# pic24rgb01-r3.net
KiCad netlist of a schematic drawn in EAGLE
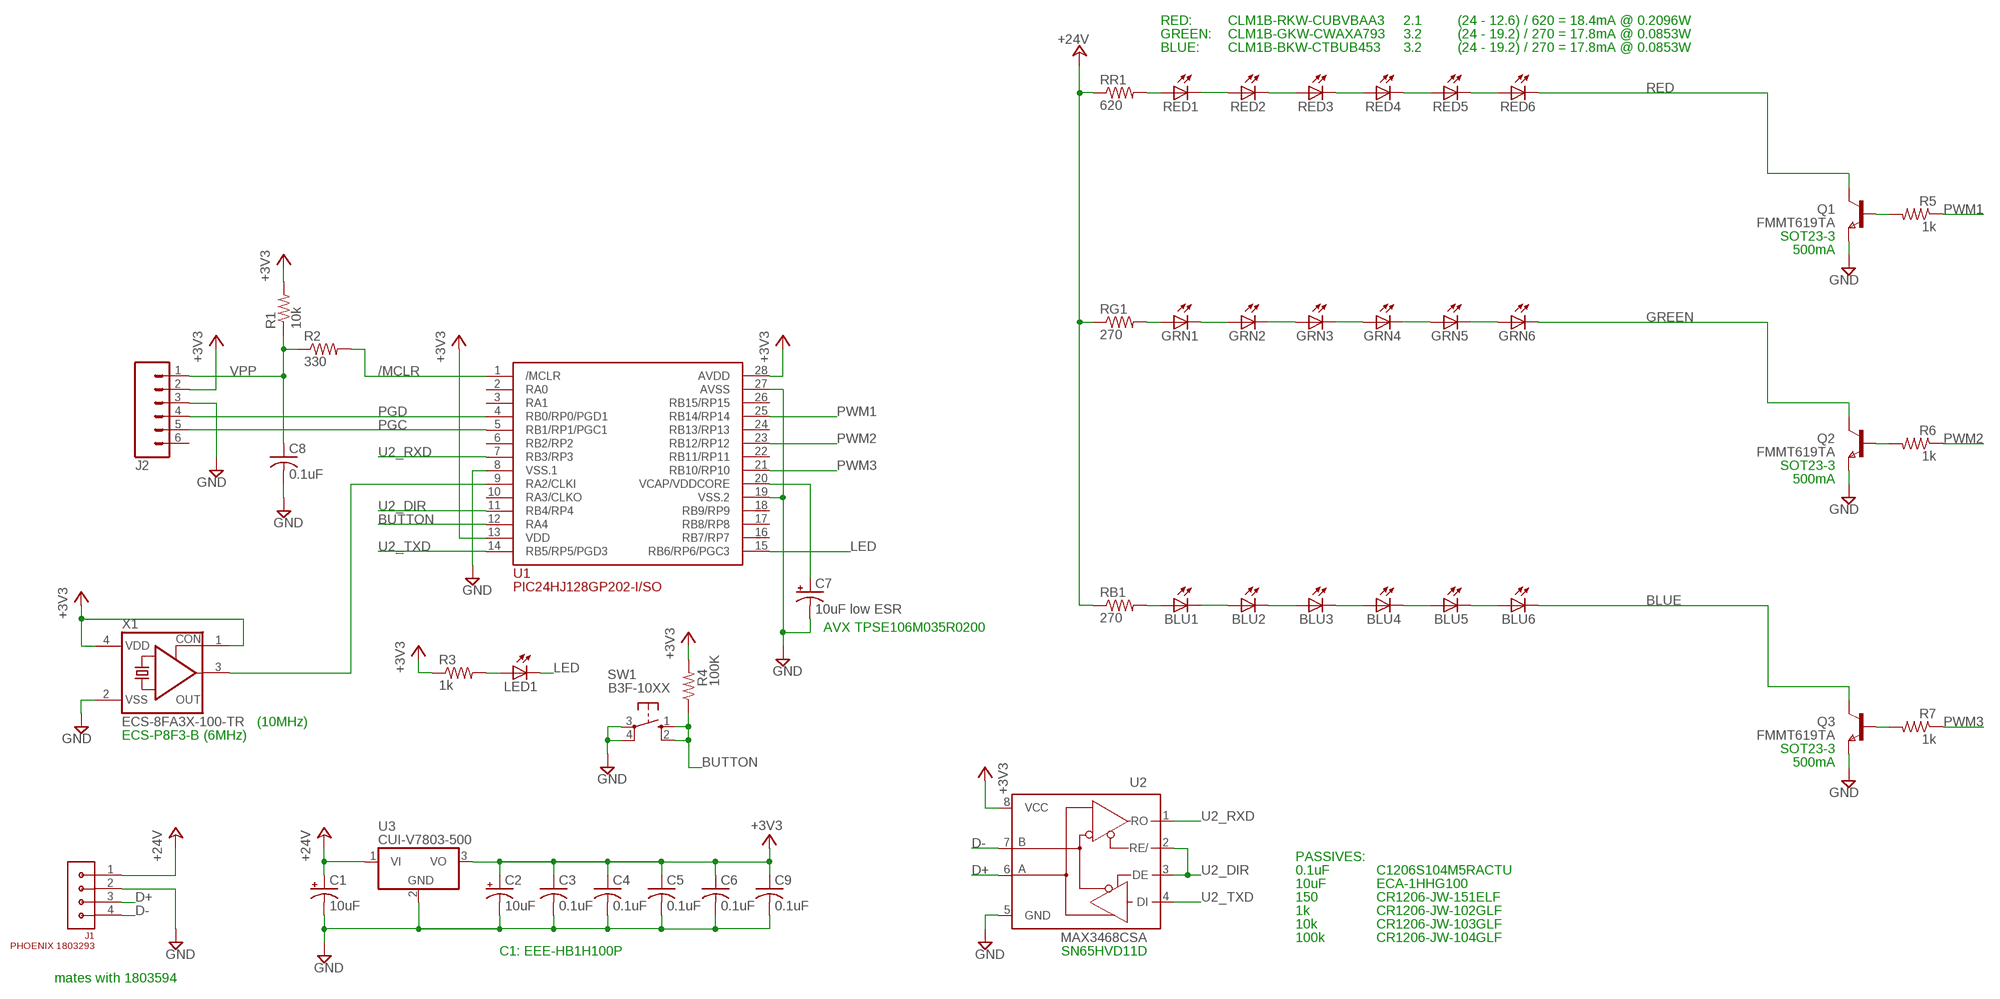
[diagram p0: schematic, sheet 1]

(export (version "E")
  (design (tool "Eeschema 10.0.6"))
  (components
    (comp (ref "BLU1")
      (value "LEDKA-3528ASYC")
      (footprint "eagle-import:KA-3528ASYC")
      (libsource (lib "eagle-import") (part "LEDKA-3528ASYC"))
    )
    (comp (ref "BLU2")
      (value "LEDKA-3528ASYC")
      (footprint "eagle-import:KA-3528ASYC")
      (libsource (lib "eagle-import") (part "LEDKA-3528ASYC"))
    )
    (comp (ref "BLU3")
      (value "LEDKA-3528ASYC")
      (footprint "eagle-import:KA-3528ASYC")
      (libsource (lib "eagle-import") (part "LEDKA-3528ASYC"))
    )
    (comp (ref "BLU4")
      (value "LEDKA-3528ASYC")
      (footprint "eagle-import:KA-3528ASYC")
      (libsource (lib "eagle-import") (part "LEDKA-3528ASYC"))
    )
    (comp (ref "BLU5")
      (value "LEDKA-3528ASYC")
      (footprint "eagle-import:KA-3528ASYC")
      (libsource (lib "eagle-import") (part "LEDKA-3528ASYC"))
    )
    (comp (ref "BLU6")
      (value "LEDKA-3528ASYC")
      (footprint "eagle-import:KA-3528ASYC")
      (libsource (lib "eagle-import") (part "LEDKA-3528ASYC"))
    )
    (comp (ref "C1")
      (value "10uF")
      (footprint "eagle-import:PANASONIC_D")
      (libsource (lib "eagle-import") (part "CPOL-USD"))
    )
    (comp (ref "C2")
      (value "10uF")
      (footprint "eagle-import:PANASONIC_D")
      (libsource (lib "eagle-import") (part "CPOL-USD"))
    )
    (comp (ref "C3")
      (value "0.1uF")
      (footprint "eagle-import:C1206")
      (libsource (lib "eagle-import") (part "C-USC1206"))
    )
    (comp (ref "C4")
      (value "0.1uF")
      (footprint "eagle-import:C1206")
      (libsource (lib "eagle-import") (part "C-USC1206"))
    )
    (comp (ref "C5")
      (value "0.1uF")
      (footprint "eagle-import:C1206")
      (libsource (lib "eagle-import") (part "C-USC1206"))
    )
    (comp (ref "C6")
      (value "0.1uF")
      (footprint "eagle-import:C1206")
      (libsource (lib "eagle-import") (part "C-USC1206"))
    )
    (comp (ref "C7")
      (value "10uF low ESR")
      (footprint "eagle-import:D_7343-31R")
      (libsource (lib "eagle-import") (part "CPOL-USD/7343-31R"))
    )
    (comp (ref "C8")
      (value "0.1uF")
      (footprint "eagle-import:C1206")
      (libsource (lib "eagle-import") (part "C-USC1206"))
    )
    (comp (ref "C9")
      (value "0.1uF")
      (footprint "eagle-import:C1206")
      (libsource (lib "eagle-import") (part "C-USC1206"))
    )
    (comp (ref "GRN1")
      (value "LEDKA-3528ASYC")
      (footprint "eagle-import:KA-3528ASYC")
      (libsource (lib "eagle-import") (part "LEDKA-3528ASYC"))
    )
    (comp (ref "GRN2")
      (value "LEDKA-3528ASYC")
      (footprint "eagle-import:KA-3528ASYC")
      (libsource (lib "eagle-import") (part "LEDKA-3528ASYC"))
    )
    (comp (ref "GRN3")
      (value "LEDKA-3528ASYC")
      (footprint "eagle-import:KA-3528ASYC")
      (libsource (lib "eagle-import") (part "LEDKA-3528ASYC"))
    )
    (comp (ref "GRN4")
      (value "LEDKA-3528ASYC")
      (footprint "eagle-import:KA-3528ASYC")
      (libsource (lib "eagle-import") (part "LEDKA-3528ASYC"))
    )
    (comp (ref "GRN5")
      (value "LEDKA-3528ASYC")
      (footprint "eagle-import:KA-3528ASYC")
      (libsource (lib "eagle-import") (part "LEDKA-3528ASYC"))
    )
    (comp (ref "GRN6")
      (value "LEDKA-3528ASYC")
      (footprint "eagle-import:KA-3528ASYC")
      (libsource (lib "eagle-import") (part "LEDKA-3528ASYC"))
    )
    (comp (ref "J1")
      (value "PHOENIX 1803293")
      (footprint "eagle-import:CON-PHOENIX-1803293-3.81-1X4")
      (libsource (lib "eagle-import") (part "CON-3.81MM-1X4-PHOENIX-1803293"))
    )
    (comp (ref "J2")
      (value "M06SIP")
      (footprint "eagle-import:1X06")
      (libsource (lib "eagle-import") (part "M06SIP"))
    )
    (comp (ref "LED1")
      (value "LED3MM")
      (footprint "eagle-import:LED3MM")
      (libsource (lib "eagle-import") (part "LED3MM"))
    )
    (comp (ref "Q1")
      (value "FMMT619TA")
      (footprint "eagle-import:SOT-23")
      (fields (field (name "MPN") "DSS20201L-7"))
      (libsource (lib "eagle-import") (part "NPNSOT23"))
    )
    (comp (ref "Q2")
      (value "FMMT619TA")
      (footprint "eagle-import:SOT-23")
      (fields (field (name "MPN") "DSS20201L-7"))
      (libsource (lib "eagle-import") (part "NPNSOT23"))
    )
    (comp (ref "Q3")
      (value "FMMT619TA")
      (footprint "eagle-import:SOT-23")
      (fields (field (name "MPN") "DSS20201L-7"))
      (libsource (lib "eagle-import") (part "NPNSOT23"))
    )
    (comp (ref "R1")
      (value "10k")
      (footprint "eagle-import:R1206")
      (libsource (lib "eagle-import") (part "R-US_R1206"))
    )
    (comp (ref "R2")
      (value "330")
      (footprint "eagle-import:R1206")
      (libsource (lib "eagle-import") (part "R-US_R1206"))
    )
    (comp (ref "R3")
      (value "1k")
      (footprint "eagle-import:R1206")
      (libsource (lib "eagle-import") (part "R-US_R1206"))
    )
    (comp (ref "R4")
      (value "100K")
      (footprint "eagle-import:M1206")
      (libsource (lib "eagle-import") (part "R-US_M1206"))
    )
    (comp (ref "R5")
      (value "1k")
      (footprint "eagle-import:R1206")
      (libsource (lib "eagle-import") (part "R-US_R1206"))
    )
    (comp (ref "R6")
      (value "1k")
      (footprint "eagle-import:R1206")
      (libsource (lib "eagle-import") (part "R-US_R1206"))
    )
    (comp (ref "R7")
      (value "1k")
      (footprint "eagle-import:R1206")
      (libsource (lib "eagle-import") (part "R-US_R1206"))
    )
    (comp (ref "RB1")
      (value "270")
      (footprint "eagle-import:R1206")
      (libsource (lib "eagle-import") (part "R-US_R1206"))
    )
    (comp (ref "RED1")
      (value "LEDKA-3528ASYC")
      (footprint "eagle-import:KA-3528ASYC")
      (libsource (lib "eagle-import") (part "LEDKA-3528ASYC"))
    )
    (comp (ref "RED2")
      (value "LEDKA-3528ASYC")
      (footprint "eagle-import:KA-3528ASYC")
      (libsource (lib "eagle-import") (part "LEDKA-3528ASYC"))
    )
    (comp (ref "RED3")
      (value "LEDKA-3528ASYC")
      (footprint "eagle-import:KA-3528ASYC")
      (libsource (lib "eagle-import") (part "LEDKA-3528ASYC"))
    )
    (comp (ref "RED4")
      (value "LEDKA-3528ASYC")
      (footprint "eagle-import:KA-3528ASYC")
      (libsource (lib "eagle-import") (part "LEDKA-3528ASYC"))
    )
    (comp (ref "RED5")
      (value "LEDKA-3528ASYC")
      (footprint "eagle-import:KA-3528ASYC")
      (libsource (lib "eagle-import") (part "LEDKA-3528ASYC"))
    )
    (comp (ref "RED6")
      (value "LEDKA-3528ASYC")
      (footprint "eagle-import:KA-3528ASYC")
      (libsource (lib "eagle-import") (part "LEDKA-3528ASYC"))
    )
    (comp (ref "RG1")
      (value "270")
      (footprint "eagle-import:R1206")
      (libsource (lib "eagle-import") (part "R-US_R1206"))
    )
    (comp (ref "RR1")
      (value "620")
      (footprint "eagle-import:R1206")
      (libsource (lib "eagle-import") (part "R-US_R1206"))
    )
    (comp (ref "SW1")
      (value "B3F-10XX")
      (footprint "eagle-import:B3F-10XX")
      (libsource (lib "eagle-import") (part "10-XX"))
    )
    (comp (ref "U1")
      (value "PIC24HJ128GP202-I/SO")
      (footprint "eagle-import:SO28W")
      (libsource (lib "eagle-import") (part "PIC24HJ128GP202-I/SO"))
    )
    (comp (ref "U2")
      (value "MAX3468CSA")
      (footprint "eagle-import:SO08")
      (fields (field (name "MPN") "MAX3468CSA+"))
      (libsource (lib "eagle-import") (part "MAX34SA68C"))
    )
    (comp (ref "U3")
      (value "CUI-V7803-500")
      (footprint "eagle-import:CUI-78XX-500")
      (libsource (lib "eagle-import") (part "CUI-V7803-500"))
    )
    (comp (ref "X1")
      (value "ECS-8FA3X-100-TR")
      (footprint "eagle-import:1100S")
      (libsource (lib "eagle-import") (part "CRYSTAL_RES-1100S"))
    )
  )
  (nets
    (net (code "1") (name "+3V3") (class "Default")
      (node (ref "C2") (pin "+") (pinfunction "+_+") (pintype "passive"))
      (node (ref "C3") (pin "1") (pinfunction "1_1") (pintype "passive"))
      (node (ref "C4") (pin "1") (pinfunction "1_1") (pintype "passive"))
      (node (ref "C5") (pin "1") (pinfunction "1_1") (pintype "passive"))
      (node (ref "C6") (pin "1") (pinfunction "1_1") (pintype "passive"))
      (node (ref "C9") (pin "1") (pinfunction "1_1") (pintype "passive"))
      (node (ref "J2") (pin "2") (pinfunction "2_2") (pintype "passive"))
      (node (ref "R1") (pin "2") (pinfunction "2_2") (pintype "passive"))
      (node (ref "R3") (pin "1") (pinfunction "1_1") (pintype "passive"))
      (node (ref "R4") (pin "2") (pinfunction "2_2") (pintype "passive"))
      (node (ref "U1") (pin "13") (pinfunction "VDD_13") (pintype "bidirectional"))
      (node (ref "U1") (pin "28") (pinfunction "AVDD_28") (pintype "bidirectional"))
      (node (ref "U2") (pin "8") (pinfunction "VCC_8") (pintype "power_in"))
      (node (ref "U3") (pin "3") (pinfunction "VO_3") (pintype "passive"))
      (node (ref "X1") (pin "1") (pinfunction "CON_1") (pintype "input"))
      (node (ref "X1") (pin "4") (pinfunction "VDD_4") (pintype "power_in"))
    )
    (net (code "2") (name "+24V") (class "Default")
      (node (ref "C1") (pin "+") (pinfunction "+_+") (pintype "passive"))
      (node (ref "J1") (pin "1") (pinfunction "1_1") (pintype "bidirectional"))
      (node (ref "RB1") (pin "1") (pinfunction "1_1") (pintype "passive"))
      (node (ref "RG1") (pin "1") (pinfunction "1_1") (pintype "passive"))
      (node (ref "RR1") (pin "1") (pinfunction "1_1") (pintype "passive"))
      (node (ref "U3") (pin "1") (pinfunction "VI_1") (pintype "input"))
    )
    (net (code "3") (name "/BLUE") (class "Default")
      (node (ref "BLU6") (pin "C") (pinfunction "C_C") (pintype "passive"))
      (node (ref "Q3") (pin "1") (pinfunction "C_1") (pintype "passive"))
    )
    (net (code "4") (name "/BUTTON") (class "Default")
      (node (ref "R4") (pin "1") (pinfunction "1_1") (pintype "passive"))
      (node (ref "SW1") (pin "1") (pinfunction "S_1") (pintype "passive"))
      (node (ref "SW1") (pin "2") (pinfunction "S1_2") (pintype "passive"))
      (node (ref "U1") (pin "12") (pinfunction "RA4_12") (pintype "bidirectional"))
    )
    (net (code "5") (name "/D+") (class "Default")
      (node (ref "J1") (pin "3") (pinfunction "3_3") (pintype "bidirectional"))
      (node (ref "U2") (pin "6") (pinfunction "A_6") (pintype "passive"))
    )
    (net (code "6") (name "/D-") (class "Default")
      (node (ref "J1") (pin "4") (pinfunction "4_4") (pintype "bidirectional"))
      (node (ref "U2") (pin "7") (pinfunction "B_7") (pintype "passive"))
    )
    (net (code "7") (name "/GREEN") (class "Default")
      (node (ref "GRN6") (pin "C") (pinfunction "C_C") (pintype "passive"))
      (node (ref "Q2") (pin "1") (pinfunction "C_1") (pintype "passive"))
    )
    (net (code "8") (name "/LED") (class "Default")
      (node (ref "LED1") (pin "K") (pinfunction "C_K") (pintype "passive"))
      (node (ref "U1") (pin "15") (pinfunction "RB6/RP6/PGC3_15") (pintype "bidirectional"))
    )
    (net (code "9") (name "/PGC") (class "Default")
      (node (ref "J2") (pin "5") (pinfunction "5_5") (pintype "passive"))
      (node (ref "U1") (pin "5") (pinfunction "RB1/RP1/PGC1_5") (pintype "bidirectional"))
    )
    (net (code "10") (name "/PGD") (class "Default")
      (node (ref "J2") (pin "4") (pinfunction "4_4") (pintype "passive"))
      (node (ref "U1") (pin "4") (pinfunction "RB0/RP0/PGD1_4") (pintype "bidirectional"))
    )
    (net (code "11") (name "/PWM1") (class "Default")
      (node (ref "R5") (pin "1") (pinfunction "1_1") (pintype "passive"))
      (node (ref "U1") (pin "25") (pinfunction "RB14/RP14_25") (pintype "bidirectional"))
    )
    (net (code "12") (name "/PWM2") (class "Default")
      (node (ref "R6") (pin "1") (pinfunction "1_1") (pintype "passive"))
      (node (ref "U1") (pin "23") (pinfunction "RB12/RP12_23") (pintype "bidirectional"))
    )
    (net (code "13") (name "/PWM3") (class "Default")
      (node (ref "R7") (pin "1") (pinfunction "1_1") (pintype "passive"))
      (node (ref "U1") (pin "21") (pinfunction "RB10/RP10_21") (pintype "bidirectional"))
    )
    (net (code "14") (name "/RED") (class "Default")
      (node (ref "Q1") (pin "1") (pinfunction "C_1") (pintype "passive"))
      (node (ref "RED6") (pin "C") (pinfunction "C_C") (pintype "passive"))
    )
    (net (code "15") (name "/U2_DIR") (class "Default")
      (node (ref "U1") (pin "11") (pinfunction "RB4/RP4_11") (pintype "bidirectional"))
      (node (ref "U2") (pin "2") (pinfunction "RE/_2") (pintype "input"))
      (node (ref "U2") (pin "3") (pinfunction "DE_3") (pintype "input"))
    )
    (net (code "16") (name "/U2_RXD") (class "Default")
      (node (ref "U1") (pin "7") (pinfunction "RB3/RP3_7") (pintype "bidirectional"))
      (node (ref "U2") (pin "1") (pinfunction "RO_1") (pintype "output"))
    )
    (net (code "17") (name "/U2_TXD") (class "Default")
      (node (ref "U1") (pin "14") (pinfunction "RB5/RP5/PGD3_14") (pintype "bidirectional"))
      (node (ref "U2") (pin "4") (pinfunction "DI_4") (pintype "input"))
    )
    (net (code "18") (name "/VPP") (class "Default")
      (node (ref "C8") (pin "1") (pinfunction "1_1") (pintype "passive"))
      (node (ref "J2") (pin "1") (pinfunction "1_1") (pintype "passive"))
      (node (ref "R1") (pin "1") (pinfunction "1_1") (pintype "passive"))
      (node (ref "R2") (pin "1") (pinfunction "1_1") (pintype "passive"))
    )
    (net (code "19") (name "/{slash}MCLR") (class "Default")
      (node (ref "R2") (pin "2") (pinfunction "2_2") (pintype "passive"))
      (node (ref "U1") (pin "1") (pinfunction "/MCLR_1") (pintype "bidirectional"))
    )
    (net (code "20") (name "GND") (class "Default")
      (node (ref "C1") (pin "-") (pinfunction "-_-") (pintype "passive"))
      (node (ref "C2") (pin "-") (pinfunction "-_-") (pintype "passive"))
      (node (ref "C3") (pin "2") (pinfunction "2_2") (pintype "passive"))
      (node (ref "C4") (pin "2") (pinfunction "2_2") (pintype "passive"))
      (node (ref "C5") (pin "2") (pinfunction "2_2") (pintype "passive"))
      (node (ref "C6") (pin "2") (pinfunction "2_2") (pintype "passive"))
      (node (ref "C7") (pin "-") (pinfunction "-_-") (pintype "passive"))
      (node (ref "C8") (pin "2") (pinfunction "2_2") (pintype "passive"))
      (node (ref "C9") (pin "2") (pinfunction "2_2") (pintype "passive"))
      (node (ref "J1") (pin "2") (pinfunction "2_2") (pintype "bidirectional"))
      (node (ref "J2") (pin "3") (pinfunction "3_3") (pintype "passive"))
      (node (ref "Q1") (pin "2") (pinfunction "E_2") (pintype "passive"))
      (node (ref "Q2") (pin "2") (pinfunction "E_2") (pintype "passive"))
      (node (ref "Q3") (pin "2") (pinfunction "E_2") (pintype "passive"))
      (node (ref "SW1") (pin "3") (pinfunction "P_3") (pintype "passive"))
      (node (ref "SW1") (pin "4") (pinfunction "P1_4") (pintype "passive"))
      (node (ref "U1") (pin "19") (pinfunction "VSS.2_19") (pintype "bidirectional"))
      (node (ref "U1") (pin "27") (pinfunction "AVSS_27") (pintype "bidirectional"))
      (node (ref "U1") (pin "8") (pinfunction "VSS.1_8") (pintype "bidirectional"))
      (node (ref "U2") (pin "5") (pinfunction "GND_5") (pintype "power_in"))
      (node (ref "U3") (pin "2") (pinfunction "GND_2") (pintype "passive"))
      (node (ref "X1") (pin "2") (pinfunction "VSS_2") (pintype "power_in"))
    )
    (net (code "21") (name "Net-(BLU1-PadA)") (class "Default")
      (node (ref "BLU1") (pin "A") (pinfunction "A_A") (pintype "passive"))
      (node (ref "RB1") (pin "2") (pinfunction "2_2") (pintype "passive"))
    )
    (net (code "22") (name "Net-(BLU1-PadC)") (class "Default")
      (node (ref "BLU1") (pin "C") (pinfunction "C_C") (pintype "passive"))
      (node (ref "BLU2") (pin "A") (pinfunction "A_A") (pintype "passive"))
    )
    (net (code "23") (name "Net-(BLU2-PadC)") (class "Default")
      (node (ref "BLU2") (pin "C") (pinfunction "C_C") (pintype "passive"))
      (node (ref "BLU3") (pin "A") (pinfunction "A_A") (pintype "passive"))
    )
    (net (code "24") (name "Net-(BLU3-PadC)") (class "Default")
      (node (ref "BLU3") (pin "C") (pinfunction "C_C") (pintype "passive"))
      (node (ref "BLU4") (pin "A") (pinfunction "A_A") (pintype "passive"))
    )
    (net (code "25") (name "Net-(BLU4-PadC)") (class "Default")
      (node (ref "BLU4") (pin "C") (pinfunction "C_C") (pintype "passive"))
      (node (ref "BLU5") (pin "A") (pinfunction "A_A") (pintype "passive"))
    )
    (net (code "26") (name "Net-(BLU5-PadC)") (class "Default")
      (node (ref "BLU5") (pin "C") (pinfunction "C_C") (pintype "passive"))
      (node (ref "BLU6") (pin "A") (pinfunction "A_A") (pintype "passive"))
    )
    (net (code "27") (name "Net-(GRN1-PadA)") (class "Default")
      (node (ref "GRN1") (pin "A") (pinfunction "A_A") (pintype "passive"))
      (node (ref "RG1") (pin "2") (pinfunction "2_2") (pintype "passive"))
    )
    (net (code "28") (name "Net-(GRN1-PadC)") (class "Default")
      (node (ref "GRN1") (pin "C") (pinfunction "C_C") (pintype "passive"))
      (node (ref "GRN2") (pin "A") (pinfunction "A_A") (pintype "passive"))
    )
    (net (code "29") (name "Net-(GRN2-PadC)") (class "Default")
      (node (ref "GRN2") (pin "C") (pinfunction "C_C") (pintype "passive"))
      (node (ref "GRN3") (pin "A") (pinfunction "A_A") (pintype "passive"))
    )
    (net (code "30") (name "Net-(GRN3-PadC)") (class "Default")
      (node (ref "GRN3") (pin "C") (pinfunction "C_C") (pintype "passive"))
      (node (ref "GRN4") (pin "A") (pinfunction "A_A") (pintype "passive"))
    )
    (net (code "31") (name "Net-(GRN4-PadC)") (class "Default")
      (node (ref "GRN4") (pin "C") (pinfunction "C_C") (pintype "passive"))
      (node (ref "GRN5") (pin "A") (pinfunction "A_A") (pintype "passive"))
    )
    (net (code "32") (name "Net-(GRN5-PadC)") (class "Default")
      (node (ref "GRN5") (pin "C") (pinfunction "C_C") (pintype "passive"))
      (node (ref "GRN6") (pin "A") (pinfunction "A_A") (pintype "passive"))
    )
    (net (code "33") (name "Net-(LED1-PadA)") (class "Default")
      (node (ref "LED1") (pin "A") (pinfunction "A_A") (pintype "passive"))
      (node (ref "R3") (pin "2") (pinfunction "2_2") (pintype "passive"))
    )
    (net (code "34") (name "Net-(Q1-B)") (class "Default")
      (node (ref "Q1") (pin "3") (pinfunction "B_3") (pintype "passive"))
      (node (ref "R5") (pin "2") (pinfunction "2_2") (pintype "passive"))
    )
    (net (code "35") (name "Net-(Q2-B)") (class "Default")
      (node (ref "Q2") (pin "3") (pinfunction "B_3") (pintype "passive"))
      (node (ref "R6") (pin "2") (pinfunction "2_2") (pintype "passive"))
    )
    (net (code "36") (name "Net-(Q3-B)") (class "Default")
      (node (ref "Q3") (pin "3") (pinfunction "B_3") (pintype "passive"))
      (node (ref "R7") (pin "2") (pinfunction "2_2") (pintype "passive"))
    )
    (net (code "37") (name "Net-(RED1-PadA)") (class "Default")
      (node (ref "RED1") (pin "A") (pinfunction "A_A") (pintype "passive"))
      (node (ref "RR1") (pin "2") (pinfunction "2_2") (pintype "passive"))
    )
    (net (code "38") (name "Net-(RED1-PadC)") (class "Default")
      (node (ref "RED1") (pin "C") (pinfunction "C_C") (pintype "passive"))
      (node (ref "RED2") (pin "A") (pinfunction "A_A") (pintype "passive"))
    )
    (net (code "39") (name "Net-(RED2-PadC)") (class "Default")
      (node (ref "RED2") (pin "C") (pinfunction "C_C") (pintype "passive"))
      (node (ref "RED3") (pin "A") (pinfunction "A_A") (pintype "passive"))
    )
    (net (code "40") (name "Net-(RED3-PadC)") (class "Default")
      (node (ref "RED3") (pin "C") (pinfunction "C_C") (pintype "passive"))
      (node (ref "RED4") (pin "A") (pinfunction "A_A") (pintype "passive"))
    )
    (net (code "41") (name "Net-(RED4-PadC)") (class "Default")
      (node (ref "RED4") (pin "C") (pinfunction "C_C") (pintype "passive"))
      (node (ref "RED5") (pin "A") (pinfunction "A_A") (pintype "passive"))
    )
    (net (code "42") (name "Net-(RED5-PadC)") (class "Default")
      (node (ref "RED5") (pin "C") (pinfunction "C_C") (pintype "passive"))
      (node (ref "RED6") (pin "A") (pinfunction "A_A") (pintype "passive"))
    )
    (net (code "43") (name "Net-(U1-RA2{slash}CLKI)") (class "Default")
      (node (ref "U1") (pin "9") (pinfunction "RA2/CLKI_9") (pintype "bidirectional"))
      (node (ref "X1") (pin "3") (pinfunction "OUT_3") (pintype "output"))
    )
    (net (code "44") (name "Net-(U1-VCAP{slash}VDDCORE)") (class "Default")
      (node (ref "C7") (pin "+") (pinfunction "+_+") (pintype "passive"))
      (node (ref "U1") (pin "20") (pinfunction "VCAP/VDDCORE_20") (pintype "bidirectional"))
    )
    (net (code "45") (name "unconnected-(J2-Pad6)") (class "Default")
      (node (ref "J2") (pin "6") (pinfunction "6_6") (pintype "passive"))
    )
    (net (code "46") (name "unconnected-(U1-RA0-Pad2)") (class "Default")
      (node (ref "U1") (pin "2") (pinfunction "RA0_2") (pintype "bidirectional"))
    )
    (net (code "47") (name "unconnected-(U1-RA1-Pad3)") (class "Default")
      (node (ref "U1") (pin "3") (pinfunction "RA1_3") (pintype "bidirectional"))
    )
    (net (code "48") (name "unconnected-(U1-RA3{slash}CLKO-Pad10)") (class "Default")
      (node (ref "U1") (pin "10") (pinfunction "RA3/CLKO_10") (pintype "bidirectional"))
    )
    (net (code "49") (name "unconnected-(U1-RB2{slash}RP2-Pad6)") (class "Default")
      (node (ref "U1") (pin "6") (pinfunction "RB2/RP2_6") (pintype "bidirectional"))
    )
    (net (code "50") (name "unconnected-(U1-RB7{slash}RP7-Pad16)") (class "Default")
      (node (ref "U1") (pin "16") (pinfunction "RB7/RP7_16") (pintype "bidirectional"))
    )
    (net (code "51") (name "unconnected-(U1-RB8{slash}RP8-Pad17)") (class "Default")
      (node (ref "U1") (pin "17") (pinfunction "RB8/RP8_17") (pintype "bidirectional"))
    )
    (net (code "52") (name "unconnected-(U1-RB9{slash}RP9-Pad18)") (class "Default")
      (node (ref "U1") (pin "18") (pinfunction "RB9/RP9_18") (pintype "bidirectional"))
    )
    (net (code "53") (name "unconnected-(U1-RB11{slash}RP11-Pad22)") (class "Default")
      (node (ref "U1") (pin "22") (pinfunction "RB11/RP11_22") (pintype "bidirectional"))
    )
    (net (code "54") (name "unconnected-(U1-RB13{slash}RP13-Pad24)") (class "Default")
      (node (ref "U1") (pin "24") (pinfunction "RB13/RP13_24") (pintype "bidirectional"))
    )
    (net (code "55") (name "unconnected-(U1-RB15{slash}RP15-Pad26)") (class "Default")
      (node (ref "U1") (pin "26") (pinfunction "RB15/RP15_26") (pintype "bidirectional"))
    )
  )
)
